# SH03_-_ETHERNET_MUXES.net
KiCad netlist of a schematic drawn in Altium Designer
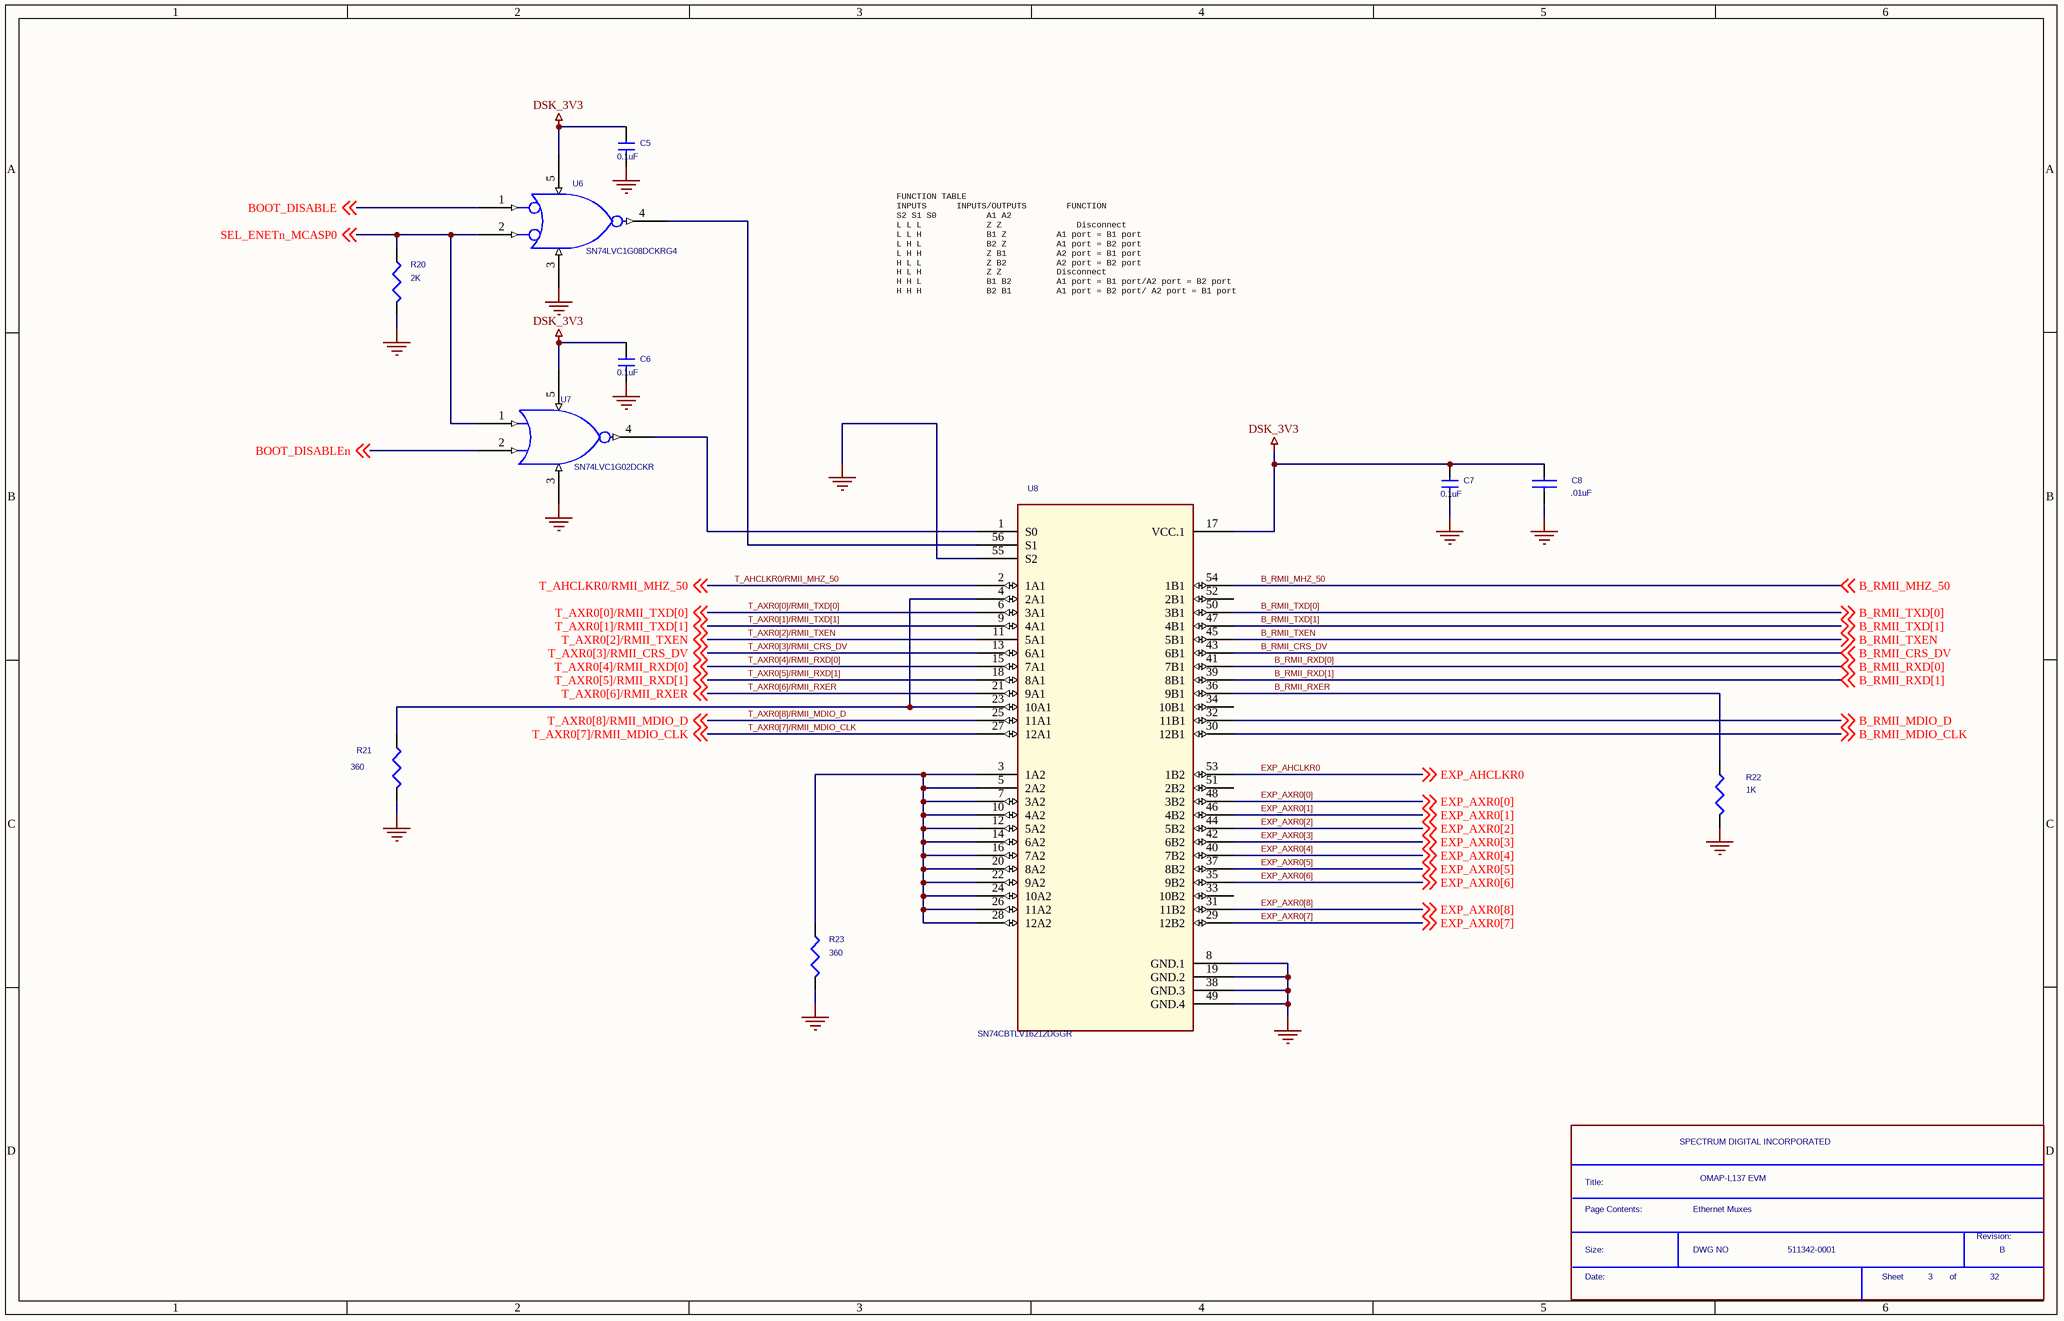
[diagram p0: SH03 - ETHERNET MUXES.SchDoc]

(export (version "E")
  (design (tool "Eeschema 10.0.6"))
  (components
    (comp (ref "C5")
      (value "0.1uF")
      (footprint "c402-25")
      (fields (field (name "PART #") "101587-1100R"))
      (libsource (lib "*") (part "CAP NP_1"))
    )
    (comp (ref "C6")
      (value "0.1uF")
      (footprint "c402-25")
      (fields (field (name "PART #") "101587-1100R"))
      (libsource (lib "*") (part "CAP NP_1"))
    )
    (comp (ref "C7")
      (value "0.1uF")
      (footprint "c402-25")
      (fields (field (name "PART #") "101587-1100R"))
      (libsource (lib "*") (part "CAP NP_1"))
    )
    (comp (ref "C8")
      (value ".01uF")
      (footprint "c402-25")
      (fields (field (name "PART #") "101587-1101R"))
      (libsource (lib "*") (part "CAP NP_0"))
    )
    (comp (ref "R20")
      (value "2K")
      (footprint "r402-25")
      (fields (field (name "PART #") "101370-2002R"))
      (libsource (lib "*") (part "R"))
    )
    (comp (ref "R21")
      (value "360")
      (footprint "r402-25")
      (fields (field (name "PART #") "101370-3601R"))
      (libsource (lib "*") (part "R"))
    )
    (comp (ref "R22")
      (value "1K")
      (footprint "r402-25")
      (fields (field (name "PART #") "101370-1002R"))
      (libsource (lib "*") (part "R_0"))
    )
    (comp (ref "R23")
      (value "360")
      (footprint "r402-25")
      (fields (field (name "PART #") "101370-3601R"))
      (libsource (lib "*") (part "R"))
    )
    (comp (ref "U6")
      (value "SN74LVC1G08DCKRG4")
      (footprint "SO5")
      (fields (field (name "PART #") "101057-0008R"))
      (libsource (lib "*") (part "1G08"))
    )
    (comp (ref "U7")
      (value "SN74LVC1G02DCKR")
      (footprint "dck-5")
      (fields (field (name "PART #") "101057-0002R"))
      (libsource (lib "*") (part "1g02_0"))
    )
    (comp (ref "U8")
      (value "SN74CBTLV16212DGGR")
      (footprint "56 pin TSSOP")
      (fields (field (name "PART #") "102693-0001R"))
      (libsource (lib "*") (part "SN74CBT16212DGGR"))
    )
  )
  (nets
    (net (code "1") (name "/B_RMII_RXER") (class "Default")
      (node (ref "R22") (pin "1") (pinfunction "1_1") (pintype "passive"))
      (node (ref "U8") (pin "36") (pinfunction "9B1_36") (pintype "bidirectional"))
    )
    (net (code "2") (name "BOOT_DISABLE") (class "Default")
      (node (ref "U6") (pin "1") (pinfunction "B_1") (pintype "input"))
    )
    (net (code "3") (name "BOOT_DISABLEn") (class "Default")
      (node (ref "U7") (pin "2") (pinfunction "A_2") (pintype "input"))
    )
    (net (code "4") (name "B_RMII_CRS_DV") (class "Default")
      (node (ref "U8") (pin "43") (pinfunction "6B1_43") (pintype "bidirectional"))
    )
    (net (code "5") (name "B_RMII_MDIO_CLK") (class "Default")
      (node (ref "U8") (pin "30") (pinfunction "12B1_30") (pintype "bidirectional"))
    )
    (net (code "6") (name "B_RMII_MDIO_D") (class "Default")
      (node (ref "U8") (pin "32") (pinfunction "11B1_32") (pintype "bidirectional"))
    )
    (net (code "7") (name "B_RMII_MHZ_50") (class "Default")
      (node (ref "U8") (pin "54") (pinfunction "1B1_54") (pintype "bidirectional"))
    )
    (net (code "8") (name "B_RMII_RXD[0]") (class "Default")
      (node (ref "U8") (pin "41") (pinfunction "7B1_41") (pintype "bidirectional"))
    )
    (net (code "9") (name "B_RMII_RXD[1]") (class "Default")
      (node (ref "U8") (pin "39") (pinfunction "8B1_39") (pintype "bidirectional"))
    )
    (net (code "10") (name "B_RMII_TXD[0]") (class "Default")
      (node (ref "U8") (pin "50") (pinfunction "3B1_50") (pintype "bidirectional"))
    )
    (net (code "11") (name "B_RMII_TXD[1]") (class "Default")
      (node (ref "U8") (pin "47") (pinfunction "4B1_47") (pintype "bidirectional"))
    )
    (net (code "12") (name "B_RMII_TXEN") (class "Default")
      (node (ref "U8") (pin "45") (pinfunction "5B1_45") (pintype "bidirectional"))
    )
    (net (code "13") (name "DSK_3V3") (class "Default")
      (node (ref "C5") (pin "1") (pinfunction "1_1") (pintype "passive"))
      (node (ref "C6") (pin "1") (pinfunction "1_1") (pintype "passive"))
      (node (ref "C7") (pin "1") (pinfunction "1_1") (pintype "passive"))
      (node (ref "C8") (pin "1") (pinfunction "1_1") (pintype "passive"))
      (node (ref "U6") (pin "5") (pinfunction "VCC_5") (pintype "input"))
      (node (ref "U7") (pin "5") (pinfunction "VCC_5") (pintype "input"))
      (node (ref "U8") (pin "17") (pinfunction "VCC.1_17") (pintype "power_in"))
    )
    (net (code "14") (name "EXP_AHCLKR0") (class "Default")
      (node (ref "U8") (pin "53") (pinfunction "1B2_53") (pintype "bidirectional"))
    )
    (net (code "15") (name "EXP_AXR0[0]") (class "Default")
      (node (ref "U8") (pin "48") (pinfunction "3B2_48") (pintype "bidirectional"))
    )
    (net (code "16") (name "EXP_AXR0[1]") (class "Default")
      (node (ref "U8") (pin "46") (pinfunction "4B2_46") (pintype "bidirectional"))
    )
    (net (code "17") (name "EXP_AXR0[2]") (class "Default")
      (node (ref "U8") (pin "44") (pinfunction "5B2_44") (pintype "bidirectional"))
    )
    (net (code "18") (name "EXP_AXR0[3]") (class "Default")
      (node (ref "U8") (pin "42") (pinfunction "6B2_42") (pintype "bidirectional"))
    )
    (net (code "19") (name "EXP_AXR0[4]") (class "Default")
      (node (ref "U8") (pin "40") (pinfunction "7B2_40") (pintype "bidirectional"))
    )
    (net (code "20") (name "EXP_AXR0[5]") (class "Default")
      (node (ref "U8") (pin "37") (pinfunction "8B2_37") (pintype "bidirectional"))
    )
    (net (code "21") (name "EXP_AXR0[6]") (class "Default")
      (node (ref "U8") (pin "35") (pinfunction "9B2_35") (pintype "bidirectional"))
    )
    (net (code "22") (name "EXP_AXR0[7]") (class "Default")
      (node (ref "U8") (pin "29") (pinfunction "12B2_29") (pintype "bidirectional"))
    )
    (net (code "23") (name "EXP_AXR0[8]") (class "Default")
      (node (ref "U8") (pin "31") (pinfunction "11B2_31") (pintype "bidirectional"))
    )
    (net (code "24") (name "GND") (class "Default")
      (node (ref "C5") (pin "2") (pinfunction "2_2") (pintype "passive"))
      (node (ref "C6") (pin "2") (pinfunction "2_2") (pintype "passive"))
      (node (ref "C7") (pin "2") (pinfunction "2_2") (pintype "passive"))
      (node (ref "C8") (pin "2") (pinfunction "2_2") (pintype "passive"))
      (node (ref "R20") (pin "2") (pinfunction "2_2") (pintype "passive"))
      (node (ref "R21") (pin "1") (pinfunction "1_1") (pintype "passive"))
      (node (ref "R22") (pin "2") (pinfunction "2_2") (pintype "passive"))
      (node (ref "R23") (pin "2") (pinfunction "2_2") (pintype "passive"))
      (node (ref "U6") (pin "3") (pinfunction "GND_3") (pintype "input"))
      (node (ref "U7") (pin "3") (pinfunction "GND_3") (pintype "input"))
      (node (ref "U8") (pin "19") (pinfunction "GND.2_19") (pintype "passive"))
      (node (ref "U8") (pin "38") (pinfunction "GND.3_38") (pintype "passive"))
      (node (ref "U8") (pin "49") (pinfunction "GND.4_49") (pintype "passive"))
      (node (ref "U8") (pin "55") (pinfunction "S2_55") (pintype "passive"))
      (node (ref "U8") (pin "8") (pinfunction "GND.1_8") (pintype "passive"))
    )
    (net (code "25") (name "Net-(U6-Y)") (class "Default")
      (node (ref "U6") (pin "4") (pinfunction "Y_4") (pintype "output"))
      (node (ref "U8") (pin "56") (pinfunction "S1_56") (pintype "passive"))
    )
    (net (code "26") (name "Net-(U7-Y)") (class "Default")
      (node (ref "U7") (pin "4") (pinfunction "Y_4") (pintype "output"))
      (node (ref "U8") (pin "1") (pinfunction "S0_1") (pintype "passive"))
    )
    (net (code "27") (name "Net-(U8-10A1)") (class "Default")
      (node (ref "R21") (pin "2") (pinfunction "2_2") (pintype "passive"))
      (node (ref "U8") (pin "23") (pinfunction "10A1_23") (pintype "bidirectional"))
      (node (ref "U8") (pin "4") (pinfunction "2A1_4") (pintype "bidirectional"))
    )
    (net (code "28") (name "Net-(U8-10A2)") (class "Default")
      (node (ref "R23") (pin "1") (pinfunction "1_1") (pintype "passive"))
      (node (ref "U8") (pin "10") (pinfunction "4A2_10") (pintype "bidirectional"))
      (node (ref "U8") (pin "12") (pinfunction "5A2_12") (pintype "bidirectional"))
      (node (ref "U8") (pin "14") (pinfunction "6A2_14") (pintype "bidirectional"))
      (node (ref "U8") (pin "16") (pinfunction "7A2_16") (pintype "bidirectional"))
      (node (ref "U8") (pin "20") (pinfunction "8A2_20") (pintype "bidirectional"))
      (node (ref "U8") (pin "22") (pinfunction "9A2_22") (pintype "bidirectional"))
      (node (ref "U8") (pin "24") (pinfunction "10A2_24") (pintype "bidirectional"))
      (node (ref "U8") (pin "26") (pinfunction "11A2_26") (pintype "bidirectional"))
      (node (ref "U8") (pin "28") (pinfunction "12A2_28") (pintype "bidirectional"))
      (node (ref "U8") (pin "3") (pinfunction "1A2_3") (pintype "passive"))
      (node (ref "U8") (pin "5") (pinfunction "2A2_5") (pintype "passive"))
      (node (ref "U8") (pin "7") (pinfunction "3A2_7") (pintype "bidirectional"))
    )
    (net (code "29") (name "SEL_ENETn_MCASP0") (class "Default")
      (node (ref "R20") (pin "1") (pinfunction "1_1") (pintype "passive"))
      (node (ref "U6") (pin "2") (pinfunction "A_2") (pintype "input"))
      (node (ref "U7") (pin "1") (pinfunction "B_1") (pintype "input"))
    )
    (net (code "30") (name "T_AHCLKR0{slash}RMII_MHZ_50") (class "Default")
      (node (ref "U8") (pin "2") (pinfunction "1A1_2") (pintype "bidirectional"))
    )
    (net (code "31") (name "T_AXR0[0]{slash}RMII_TXD[0]") (class "Default")
      (node (ref "U8") (pin "6") (pinfunction "3A1_6") (pintype "bidirectional"))
    )
    (net (code "32") (name "T_AXR0[1]{slash}RMII_TXD[1]") (class "Default")
      (node (ref "U8") (pin "9") (pinfunction "4A1_9") (pintype "bidirectional"))
    )
    (net (code "33") (name "T_AXR0[2]{slash}RMII_TXEN") (class "Default")
      (node (ref "U8") (pin "11") (pinfunction "5A1_11") (pintype "passive"))
    )
    (net (code "34") (name "T_AXR0[3]{slash}RMII_CRS_DV") (class "Default")
      (node (ref "U8") (pin "13") (pinfunction "6A1_13") (pintype "bidirectional"))
    )
    (net (code "35") (name "T_AXR0[4]{slash}RMII_RXD[0]") (class "Default")
      (node (ref "U8") (pin "15") (pinfunction "7A1_15") (pintype "bidirectional"))
    )
    (net (code "36") (name "T_AXR0[5]{slash}RMII_RXD[1]") (class "Default")
      (node (ref "U8") (pin "18") (pinfunction "8A1_18") (pintype "bidirectional"))
    )
    (net (code "37") (name "T_AXR0[6]{slash}RMII_RXER") (class "Default")
      (node (ref "U8") (pin "21") (pinfunction "9A1_21") (pintype "bidirectional"))
    )
    (net (code "38") (name "T_AXR0[7]{slash}RMII_MDIO_CLK") (class "Default")
      (node (ref "U8") (pin "27") (pinfunction "12A1_27") (pintype "bidirectional"))
    )
    (net (code "39") (name "T_AXR0[8]{slash}RMII_MDIO_D") (class "Default")
      (node (ref "U8") (pin "25") (pinfunction "11A1_25") (pintype "bidirectional"))
    )
    (net (code "40") (name "unconnected-(U8-2B1-Pad52)") (class "Default")
      (node (ref "U8") (pin "52") (pinfunction "2B1_52") (pintype "bidirectional"))
    )
    (net (code "41") (name "unconnected-(U8-2B2-Pad51)") (class "Default")
      (node (ref "U8") (pin "51") (pinfunction "2B2_51") (pintype "bidirectional"))
    )
    (net (code "42") (name "unconnected-(U8-10B1-Pad34)") (class "Default")
      (node (ref "U8") (pin "34") (pinfunction "10B1_34") (pintype "bidirectional"))
    )
    (net (code "43") (name "unconnected-(U8-10B2-Pad33)") (class "Default")
      (node (ref "U8") (pin "33") (pinfunction "10B2_33") (pintype "bidirectional"))
    )
  )
)
